# 780-00012-P4_Sch_M2_Focus_Drive.net
KiCad netlist of a schematic drawn in Altium Designer
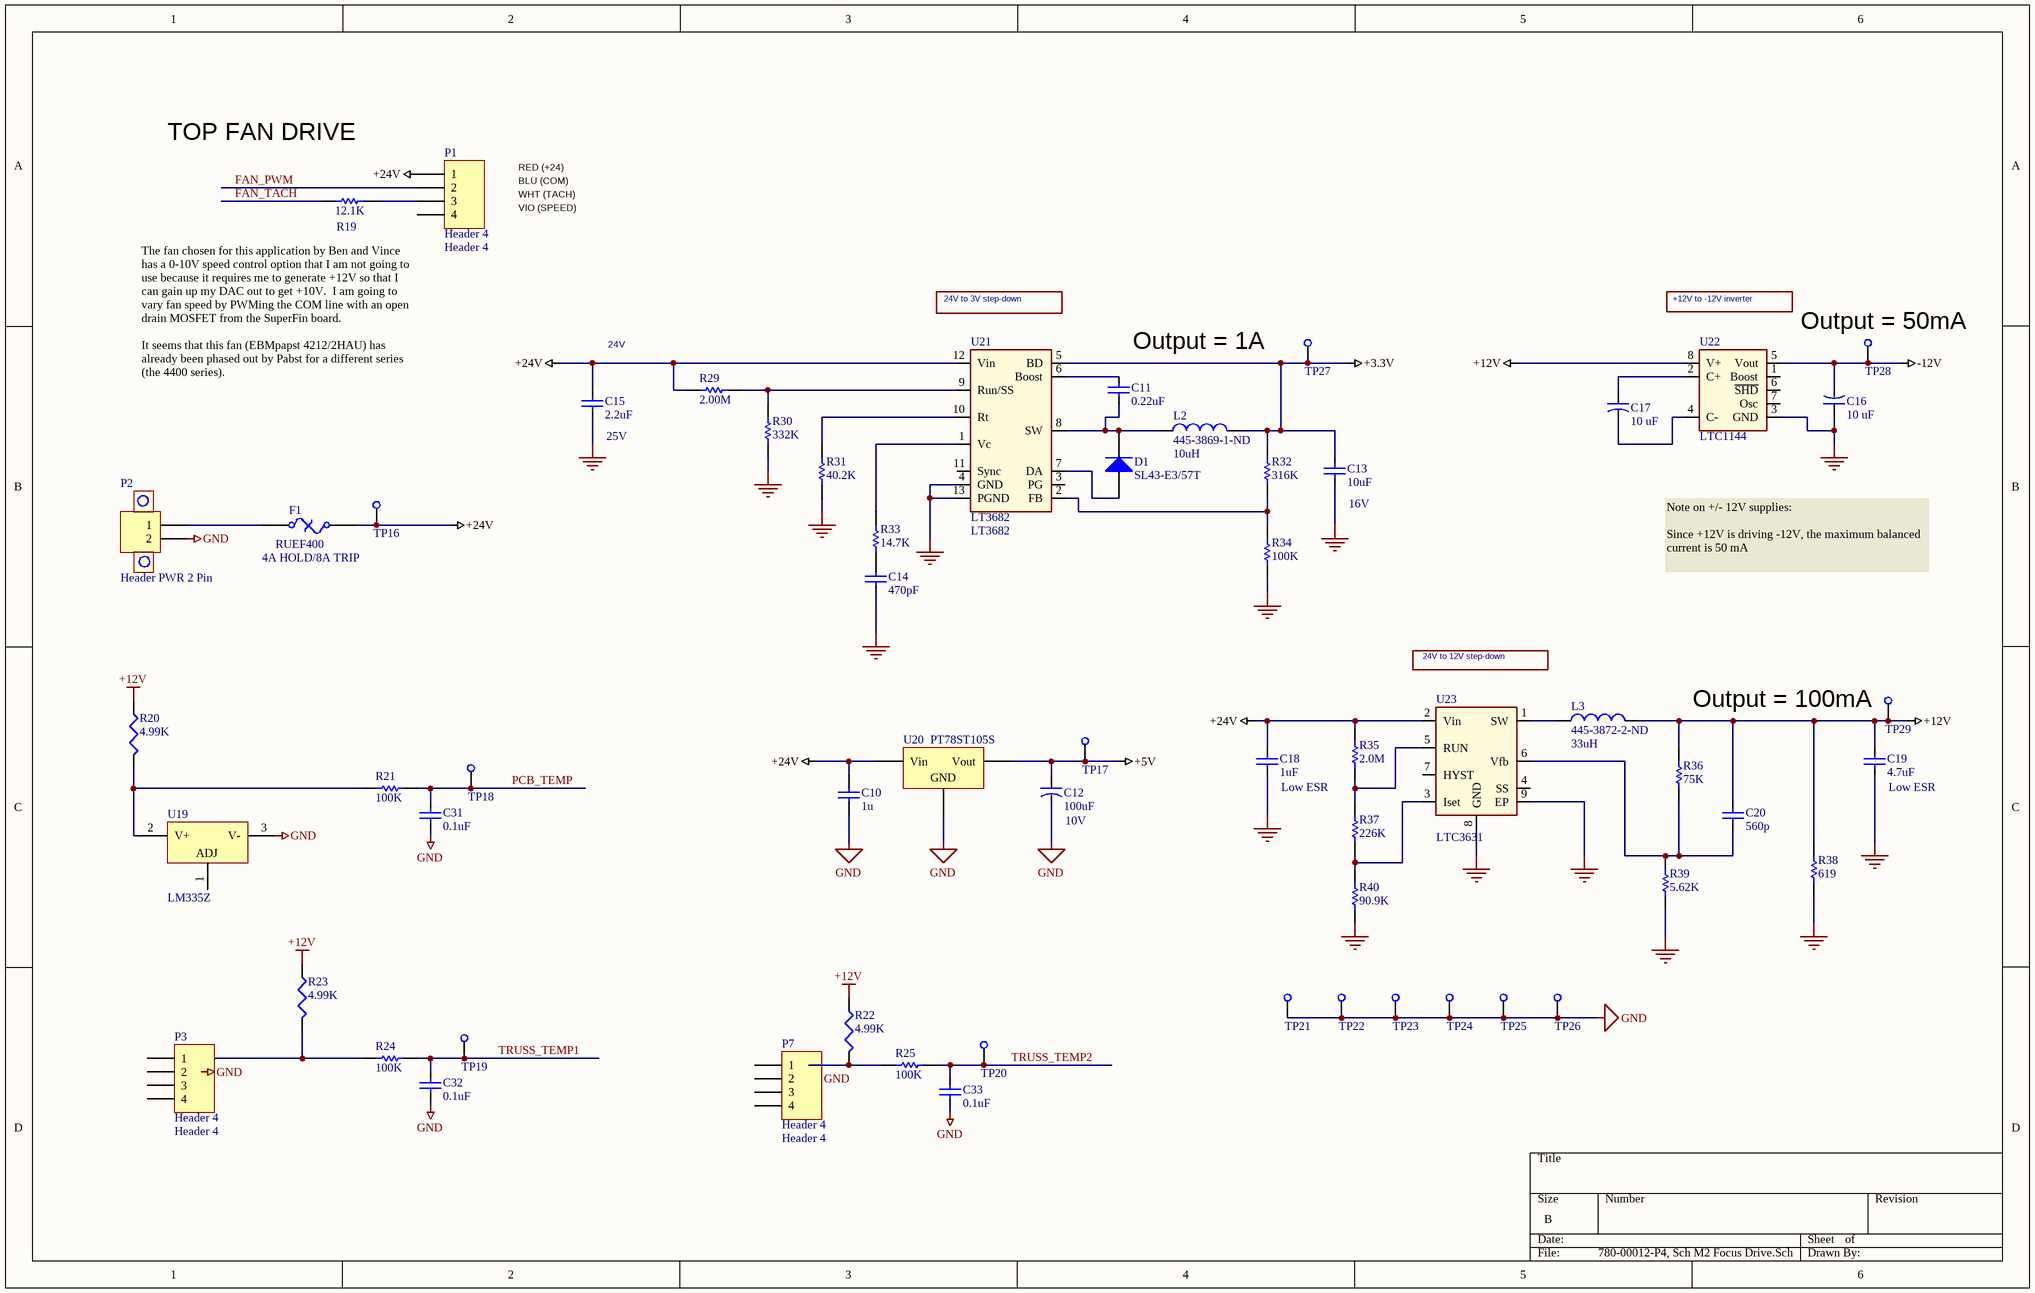
[diagram p0: 780-00012-P4, Sch M2 Focus Drive.SchDoc]

(export (version "E")
  (design (tool "Eeschema 10.0.6"))
  (components
    (comp (ref "C10")
      (value "1u")
      (footprint "2012[0805]")
      (description "Capacitor")
      (fields (field (name "MANUFACTURER") "Taiyo Yuden"))
      (libsource (lib "Miscellaneous Devices") (part "Cap"))
    )
    (comp (ref "C11")
      (value "0.22uF")
      (footprint "SMD_0805")
      (description "Capacitor")
      (fields (field (name "Comment") "Cap SMD"))
      (libsource (lib "Richs Schematic Components") (part "Cap SMD"))
    )
    (comp (ref "C12")
      (value "10V")
      (footprint "SMD_CAP_7343")
      (description "outline 6.0mm x 3.2mm")
      (fields (field (name "MANUFACTURER") "kEMET") (field (name "ALTIUM_VALUE") "100uF"))
      (libsource (lib "Richs Schematic Components") (part "Cap Tant 35V"))
    )
    (comp (ref "C13")
      (value "16V")
      (footprint "SMD_0805")
      (description "Capacitor")
      (fields (field (name "ALTIUM_VALUE") "10uF"))
      (libsource (lib "Richs Schematic Components") (part "Cap SMD"))
    )
    (comp (ref "C14")
      (value "470pF")
      (footprint "SMD_0805")
      (description "Capacitor")
      (fields (field (name "Comment") "Cap SMD"))
      (libsource (lib "Richs Schematic Components") (part "Cap SMD"))
    )
    (comp (ref "C15")
      (value "25V")
      (footprint "SMD_0805")
      (description "Capacitor")
      (fields (field (name "MANUFACTURER") "Taiyo Yuden") (field (name "ALTIUM_VALUE") "2.2uF"))
      (libsource (lib "Richs Schematic Components") (part "Cap SMD"))
    )
    (comp (ref "C16")
      (value "10 uF")
      (footprint "SMD_CAP_3216")
      (description "outline 3.2mm x 1.6mm")
      (fields (field (name "MANUFACTURER") "KEMET") (field (name "Comment") "16V"))
      (libsource (lib "Richs Schematic Components") (part "Cap Tant 16V"))
    )
    (comp (ref "C17")
      (value "10 uF")
      (footprint "SMD_CAP_3216")
      (description "outline 3.2mm x 1.6mm")
      (fields (field (name "MANUFACTURER") "KEMET") (field (name "Comment") "16V"))
      (libsource (lib "Richs Schematic Components") (part "Cap Tant 16V"))
    )
    (comp (ref "C18")
      (value "Low ESR")
      (footprint "SMD_1206")
      (description "Capacitor")
      (fields (field (name "MANUFACTURER") "TDK") (field (name "ALTIUM_VALUE") "1uF"))
      (libsource (lib "Richs Schematic Components") (part "Cap SMD"))
    )
    (comp (ref "C19")
      (value "Low ESR")
      (footprint "SMD_1206")
      (description "Capacitor")
      (fields (field (name "MANUFACTURER") "TDK") (field (name "ALTIUM_VALUE") "4.7uF"))
      (libsource (lib "Richs Schematic Components") (part "Cap SMD"))
    )
    (comp (ref "C20")
      (value "560p")
      (footprint "SMD_0805")
      (description "Capacitor")
      (fields (field (name "Comment") "Cap SMD"))
      (libsource (lib "Richs Schematic Components") (part "Cap SMD"))
    )
    (comp (ref "C31")
      (value "0.1uF")
      (footprint "SMD_0805")
      (description "Capacitor")
      (fields (field (name "MANUFACTURER") "AVX") (field (name "Comment") "Cap SMD"))
      (libsource (lib "Richs Schematic Components") (part "Cap SMD"))
    )
    (comp (ref "C32")
      (value "0.1uF")
      (footprint "SMD_0805")
      (description "Capacitor")
      (fields (field (name "MANUFACTURER") "AVX") (field (name "Comment") "Cap SMD"))
      (libsource (lib "Richs Schematic Components") (part "Cap SMD"))
    )
    (comp (ref "C33")
      (value "0.1uF")
      (footprint "SMD_0805")
      (description "Capacitor")
      (fields (field (name "MANUFACTURER") "AVX") (field (name "Comment") "Cap SMD"))
      (libsource (lib "Richs Schematic Components") (part "Cap SMD"))
    )
    (comp (ref "D1")
      (value "SL43-E3/57T")
      (footprint "SMC")
      (description "Default Diode")
      (fields (field (name "MANUFACTURER") "Vishay/Dale"))
      (libsource (lib "Miscellaneous Devices") (part "Diode"))
    )
    (comp (ref "F1")
      (value "RUEF400")
      (footprint "PolySwitch Radial 0.2")
      (description "PolySwitch RUE Series")
      (fields
        (field (name "MANUFACTURER") "Tyco Electronics")
        (field (name "ALTIUM_VALUE") "4A HOLD/8A TRIP")
      )
      (libsource (lib "Richs Schematic Components") (part "Fuse Thermal"))
    )
    (comp (ref "L2")
      (value "445-3869-1-ND")
      (footprint "Inductor TDC SLF")
      (description "Inductor")
      (fields (field (name "MANUFACTURER") "TDK") (field (name "ALTIUM_VALUE") "10uH"))
      (libsource (lib "Richs Schematic Components") (part "Inductor SMD 10uH 1.8A"))
    )
    (comp (ref "L3")
      (value "445-3872-2-ND")
      (footprint "Inductor TDC SLF")
      (description "Inductor")
      (fields (field (name "MANUFACTURER") "TDK") (field (name "ALTIUM_VALUE") "33uH"))
      (libsource (lib "Richs Schematic Components") (part "Inductor SMD 10uH 1.8A"))
    )
    (comp (ref "P1")
      (value "Header 4")
      (footprint "HDR1X4 for IDC")
      (description "Header, 4-Pin")
      (fields (field (name "ALTIUM_VALUE") "Header 4"))
      (libsource (lib "Richs Schematic Components") (part "Header 4"))
    )
    (comp (ref "P2")
      (value "Header PWR 2 Pin")
      (footprint "HDR-2 pin w/screw")
      (description "Header, 2-Pin")
      (libsource (lib "Richs Schematic Components") (part "Header 2 PWR"))
    )
    (comp (ref "P3")
      (value "Header 4")
      (footprint "HDR1X4 for IDC")
      (description "Header, 4-Pin")
      (fields (field (name "ALTIUM_VALUE") "Header 4"))
      (libsource (lib "Richs Schematic Components") (part "Header 4"))
    )
    (comp (ref "P7")
      (value "Header 4")
      (footprint "HDR1X4 for IDC")
      (description "Header, 4-Pin")
      (fields (field (name "ALTIUM_VALUE") "Header 4"))
      (libsource (lib "Richs Schematic Components") (part "Header 4"))
    )
    (comp (ref "R19")
      (value "12.1K")
      (footprint "SMD_0805")
      (description "Resistor 0805")
      (fields (field (name "MANUFACTURER") "Vishay/Dale") (field (name "Comment") "Res 0805"))
      (libsource (lib "Richs Schematic Components") (part "Res SMD"))
    )
    (comp (ref "R20")
      (value "4.99K")
      (footprint "smd_0805")
      (description "Resistor")
      (fields (field (name "MANUFACTURER") "DALE") (field (name "Comment") "Res3"))
      (libsource (lib "Miscellaneous Devices") (part "Res3"))
    )
    (comp (ref "R21")
      (value "100K")
      (footprint "SMD_0805")
      (description "Resistor")
      (fields (field (name "MANUFACTURER") "Vishay/Dale") (field (name "Comment") "Res SMD"))
      (libsource (lib "Richs Schematic Components") (part "Res SMD"))
    )
    (comp (ref "R22")
      (value "4.99K")
      (footprint "smd_0805")
      (description "Resistor")
      (fields (field (name "MANUFACTURER") "DALE") (field (name "Comment") "Res3"))
      (libsource (lib "Miscellaneous Devices") (part "Res3"))
    )
    (comp (ref "R23")
      (value "4.99K")
      (footprint "smd_0805")
      (description "Resistor")
      (fields (field (name "MANUFACTURER") "DALE") (field (name "Comment") "Res3"))
      (libsource (lib "Miscellaneous Devices") (part "Res3"))
    )
    (comp (ref "R24")
      (value "100K")
      (footprint "SMD_0805")
      (description "Resistor")
      (fields (field (name "MANUFACTURER") "Vishay/Dale") (field (name "Comment") "Res SMD"))
      (libsource (lib "Richs Schematic Components") (part "Res SMD"))
    )
    (comp (ref "R25")
      (value "100K")
      (footprint "SMD_0805")
      (description "Resistor")
      (fields (field (name "MANUFACTURER") "Vishay/Dale") (field (name "Comment") "Res SMD"))
      (libsource (lib "Richs Schematic Components") (part "Res SMD"))
    )
    (comp (ref "R29")
      (value "2.00M")
      (footprint "SMD_0805")
      (description "Resistor 0805")
      (fields (field (name "MANUFACTURER") "Vishay/Dale") (field (name "Comment") "Res 0805"))
      (libsource (lib "Richs Schematic Components") (part "Res SMD"))
    )
    (comp (ref "R30")
      (value "332K")
      (footprint "SMD_0805")
      (description "Resistor 0805")
      (fields (field (name "MANUFACTURER") "Vishay/Dale") (field (name "Comment") "Res 0805"))
      (libsource (lib "Richs Schematic Components") (part "Res SMD"))
    )
    (comp (ref "R31")
      (value "40.2K")
      (footprint "SMD_0805")
      (description "Resistor 0805")
      (fields (field (name "MANUFACTURER") "Vishay/Dale") (field (name "Comment") "Res 0805"))
      (libsource (lib "Richs Schematic Components") (part "Res SMD"))
    )
    (comp (ref "R32")
      (value "316K")
      (footprint "SMD_0805")
      (description "Resistor 0805")
      (fields (field (name "MANUFACTURER") "Vishay/Dale") (field (name "Comment") "Res 0805"))
      (libsource (lib "Richs Schematic Components") (part "Res SMD"))
    )
    (comp (ref "R33")
      (value "14.7K")
      (footprint "SMD_0805")
      (description "Resistor 0805")
      (fields (field (name "MANUFACTURER") "Vishay/Dale") (field (name "Comment") "Res 0805"))
      (libsource (lib "Richs Schematic Components") (part "Res SMD"))
    )
    (comp (ref "R34")
      (value "100K")
      (footprint "SMD_0805")
      (description "Resistor 0805")
      (fields (field (name "MANUFACTURER") "Vishay/Dale") (field (name "Comment") "Res 0805"))
      (libsource (lib "Richs Schematic Components") (part "Res SMD"))
    )
    (comp (ref "R35")
      (value "2.0M")
      (footprint "SMD_0805")
      (description "Resistor 0805")
      (fields (field (name "MANUFACTURER") "Vishay/Dale") (field (name "Comment") "Res 0805"))
      (libsource (lib "Richs Schematic Components") (part "Res SMD"))
    )
    (comp (ref "R36")
      (value "75K")
      (footprint "SMD_0805")
      (description "Resistor 0805")
      (fields (field (name "MANUFACTURER") "Vishay/Dale") (field (name "Comment") "Res 0805"))
      (libsource (lib "Richs Schematic Components") (part "Res SMD"))
    )
    (comp (ref "R37")
      (value "226K")
      (footprint "SMD_0805")
      (description "Resistor 0805")
      (fields (field (name "MANUFACTURER") "Vishay/Dale") (field (name "Comment") "Res 0805"))
      (libsource (lib "Richs Schematic Components") (part "Res SMD"))
    )
    (comp (ref "R38")
      (value "619")
      (footprint "SMD_0805")
      (description "Resistor 0805")
      (fields (field (name "MANUFACTURER") "Vishay/Dale") (field (name "Comment") "Res 0805"))
      (libsource (lib "Richs Schematic Components") (part "Res SMD"))
    )
    (comp (ref "R39")
      (value "5.62K")
      (footprint "SMD_0805")
      (description "Resistor 0805")
      (fields (field (name "MANUFACTURER") "Vishay/Dale") (field (name "Comment") "Res 0805"))
      (libsource (lib "Richs Schematic Components") (part "Res SMD"))
    )
    (comp (ref "R40")
      (value "90.9K")
      (footprint "SMD_0805")
      (description "Resistor 0805")
      (fields (field (name "MANUFACTURER") "Vishay/Dale") (field (name "Comment") "Res 0805"))
      (libsource (lib "Richs Schematic Components") (part "Res SMD"))
    )
    (comp (ref "TP16")
      (value "Test Point SMD")
      (footprint "SMD_TEST POINT")
      (description "SMD loop test point")
      (libsource (lib "Richs Schematic Components") (part "Test Point SMD"))
    )
    (comp (ref "TP17")
      (value "Test Point SMD")
      (footprint "SMD_TEST POINT")
      (description "SMD loop test point")
      (libsource (lib "Richs Schematic Components") (part "Test Point SMD"))
    )
    (comp (ref "TP18")
      (value "Test Point SMD")
      (footprint "SMD_TEST POINT")
      (description "SMD loop test point")
      (libsource (lib "Richs Schematic Components") (part "Test Point SMD"))
    )
    (comp (ref "TP19")
      (value "Test Point SMD")
      (footprint "SMD_TEST POINT")
      (description "SMD loop test point")
      (libsource (lib "Richs Schematic Components") (part "Test Point SMD"))
    )
    (comp (ref "TP20")
      (value "Test Point SMD")
      (footprint "SMD_TEST POINT")
      (description "SMD loop test point")
      (libsource (lib "Richs Schematic Components") (part "Test Point SMD"))
    )
    (comp (ref "TP21")
      (value "Test Point SMD")
      (footprint "SMD_TEST POINT")
      (description "SMD loop test point")
      (libsource (lib "Richs Schematic Components") (part "Test Point SMD"))
    )
    (comp (ref "TP22")
      (value "Test Point SMD")
      (footprint "SMD_TEST POINT")
      (description "SMD loop test point")
      (libsource (lib "Richs Schematic Components") (part "Test Point SMD"))
    )
    (comp (ref "TP23")
      (value "Test Point SMD")
      (footprint "SMD_TEST POINT")
      (description "SMD loop test point")
      (libsource (lib "Richs Schematic Components") (part "Test Point SMD"))
    )
    (comp (ref "TP24")
      (value "Test Point SMD")
      (footprint "SMD_TEST POINT")
      (description "SMD loop test point")
      (libsource (lib "Richs Schematic Components") (part "Test Point SMD"))
    )
    (comp (ref "TP25")
      (value "Test Point SMD")
      (footprint "SMD_TEST POINT")
      (description "SMD loop test point")
      (libsource (lib "Richs Schematic Components") (part "Test Point SMD"))
    )
    (comp (ref "TP26")
      (value "Test Point SMD")
      (footprint "SMD_TEST POINT")
      (description "SMD loop test point")
      (libsource (lib "Richs Schematic Components") (part "Test Point SMD"))
    )
    (comp (ref "TP27")
      (value "Test Point SMD")
      (footprint "SMD_TEST POINT")
      (description "SMD loop test point")
      (libsource (lib "Richs Schematic Components") (part "Test Point SMD"))
    )
    (comp (ref "TP28")
      (value "Test Point SMD")
      (footprint "SMD_TEST POINT")
      (description "SMD loop test point")
      (libsource (lib "Richs Schematic Components") (part "Test Point SMD"))
    )
    (comp (ref "TP29")
      (value "Test Point SMD")
      (footprint "SMD_TEST POINT")
      (description "SMD loop test point")
      (libsource (lib "Richs Schematic Components") (part "Test Point SMD"))
    )
    (comp (ref "U19")
      (value "LM335Z")
      (footprint "Z03A")
      (description "Precision Temperature Sensor")
      (fields (field (name "MANUFACTURER") "National Semiconductor"))
      (libsource (lib "NSC Temperature Sensor") (part "LM335Z"))
    )
    (comp (ref "U20")
      (value "PT78ST105S")
      (footprint "PSIP_3_SMD")
      (description "Voltage Regulator")
      (fields (field (name "MANUFACTURER") "Texas Instruments"))
      (libsource (lib "Miscellaneous Devices") (part "Volt Reg"))
    )
    (comp (ref "U21")
      (value "LT3682")
      (footprint "DD12/DFN12")
      (description "1A uPwr Step-Down switching regulator")
      (fields (field (name "MANUFACTURER") "Linear") (field (name "ALTIUM_VALUE") "LT3682"))
      (libsource (lib "Richs Schematic Components") (part "LT3682"))
    )
    (comp (ref "U22")
      (value "LTC1144")
      (footprint "S8_M")
      (description "IC VOLT CONV SW-CAP W/SHTDN8SOIC")
      (fields (field (name "MANUFACTURER") "Linear"))
      (libsource (lib "Richs Schematic Components") (part "LTC1144"))
    )
    (comp (ref "U23")
      (value "LTC3631")
      (footprint "DD8/DFN8")
      (description "IC CONV STP-DWN ADJ 8-DFN")
      (fields (field (name "MANUFACTURER") "Linear"))
      (libsource (lib "Richs Schematic Components") (part "LTC3631"))
    )
  )
  (nets
    (net (code "1") (name "+3.3V") (class "Default")
      (node (ref "C13") (pin "2") (pinfunction "2_2") (pintype "passive"))
      (node (ref "L2") (pin "2") (pinfunction "2_2") (pintype "passive"))
      (node (ref "R32") (pin "2") (pinfunction "2_2") (pintype "passive"))
      (node (ref "TP27") (pin "1") (pinfunction "TP_1") (pintype "passive"))
      (node (ref "U21") (pin "5") (pinfunction "BD_5") (pintype "passive"))
    )
    (net (code "2") (name "+5V") (class "Default")
      (node (ref "C12") (pin "pos") (pinfunction "1_pos") (pintype "passive"))
      (node (ref "TP17") (pin "1") (pinfunction "TP_1") (pintype "passive"))
      (node (ref "U20") (pin "3") (pinfunction "Vout_3") (pintype "passive"))
    )
    (net (code "3") (name "+12V") (class "Default")
      (node (ref "C19") (pin "2") (pinfunction "2_2") (pintype "passive"))
      (node (ref "C20") (pin "2") (pinfunction "2_2") (pintype "passive"))
      (node (ref "L3") (pin "2") (pinfunction "2_2") (pintype "passive"))
      (node (ref "R20") (pin "1") (pinfunction "1_1") (pintype "passive"))
      (node (ref "R22") (pin "1") (pinfunction "1_1") (pintype "passive"))
      (node (ref "R23") (pin "1") (pinfunction "1_1") (pintype "passive"))
      (node (ref "R36") (pin "2") (pinfunction "2_2") (pintype "passive"))
      (node (ref "R38") (pin "2") (pinfunction "2_2") (pintype "passive"))
      (node (ref "TP29") (pin "1") (pinfunction "TP_1") (pintype "passive"))
      (node (ref "U22") (pin "8") (pinfunction "V+_8") (pintype "power_in"))
    )
    (net (code "4") (name "+24V") (class "Default")
      (node (ref "C10") (pin "1") (pinfunction "1_1") (pintype "passive"))
      (node (ref "C15") (pin "2") (pinfunction "2_2") (pintype "passive"))
      (node (ref "C18") (pin "2") (pinfunction "2_2") (pintype "passive"))
      (node (ref "F1") (pin "2") (pinfunction "2_2") (pintype "passive"))
      (node (ref "P1") (pin "1") (pinfunction "1_1") (pintype "passive"))
      (node (ref "R29") (pin "1") (pinfunction "1_1") (pintype "passive"))
      (node (ref "R35") (pin "2") (pinfunction "2_2") (pintype "passive"))
      (node (ref "TP16") (pin "1") (pinfunction "TP_1") (pintype "passive"))
      (node (ref "U20") (pin "1") (pinfunction "Vin_1") (pintype "passive"))
      (node (ref "U21") (pin "12") (pinfunction "Vin_12") (pintype "passive"))
      (node (ref "U23") (pin "2") (pinfunction "Vin_2") (pintype "passive"))
    )
    (net (code "5") (name "-12V") (class "Default")
      (node (ref "C16") (pin "2") (pinfunction "2_2") (pintype "passive"))
      (node (ref "TP28") (pin "1") (pinfunction "TP_1") (pintype "passive"))
      (node (ref "U22") (pin "5") (pinfunction "Vout_5") (pintype "passive"))
    )
    (net (code "6") (name "/FAN_PWM") (class "Default")
      (node (ref "P1") (pin "2") (pinfunction "2_2") (pintype "passive"))
    )
    (net (code "7") (name "/FAN_TACH") (class "Default")
      (node (ref "R19") (pin "1") (pinfunction "1_1") (pintype "passive"))
    )
    (net (code "8") (name "/PCB_TEMP") (class "Default")
      (node (ref "C31") (pin "2") (pinfunction "2_2") (pintype "passive"))
      (node (ref "R21") (pin "1") (pinfunction "1_1") (pintype "passive"))
      (node (ref "TP18") (pin "1") (pinfunction "TP_1") (pintype "passive"))
    )
    (net (code "9") (name "/TRUSS_TEMP1") (class "Default")
      (node (ref "C32") (pin "2") (pinfunction "2_2") (pintype "passive"))
      (node (ref "R24") (pin "1") (pinfunction "1_1") (pintype "passive"))
      (node (ref "TP19") (pin "1") (pinfunction "TP_1") (pintype "passive"))
    )
    (net (code "10") (name "/TRUSS_TEMP2") (class "Default")
      (node (ref "C33") (pin "2") (pinfunction "2_2") (pintype "passive"))
      (node (ref "R25") (pin "1") (pinfunction "1_1") (pintype "passive"))
      (node (ref "TP20") (pin "1") (pinfunction "TP_1") (pintype "passive"))
    )
    (net (code "11") (name "GND") (class "Default")
      (node (ref "C10") (pin "2") (pinfunction "2_2") (pintype "passive"))
      (node (ref "C12") (pin "neg") (pinfunction "2_neg") (pintype "passive"))
      (node (ref "C13") (pin "1") (pinfunction "1_1") (pintype "passive"))
      (node (ref "C14") (pin "1") (pinfunction "1_1") (pintype "passive"))
      (node (ref "C15") (pin "1") (pinfunction "1_1") (pintype "passive"))
      (node (ref "C16") (pin "1") (pinfunction "1_1") (pintype "passive"))
      (node (ref "C18") (pin "1") (pinfunction "1_1") (pintype "passive"))
      (node (ref "C19") (pin "1") (pinfunction "1_1") (pintype "passive"))
      (node (ref "C31") (pin "1") (pinfunction "1_1") (pintype "passive"))
      (node (ref "C32") (pin "1") (pinfunction "1_1") (pintype "passive"))
      (node (ref "C33") (pin "1") (pinfunction "1_1") (pintype "passive"))
      (node (ref "P2") (pin "2") (pinfunction "2_2") (pintype "passive"))
      (node (ref "R30") (pin "1") (pinfunction "1_1") (pintype "passive"))
      (node (ref "R31") (pin "1") (pinfunction "1_1") (pintype "passive"))
      (node (ref "R34") (pin "1") (pinfunction "1_1") (pintype "passive"))
      (node (ref "R38") (pin "1") (pinfunction "1_1") (pintype "passive"))
      (node (ref "R39") (pin "1") (pinfunction "1_1") (pintype "passive"))
      (node (ref "R40") (pin "1") (pinfunction "1_1") (pintype "passive"))
      (node (ref "TP21") (pin "1") (pinfunction "TP_1") (pintype "passive"))
      (node (ref "TP22") (pin "1") (pinfunction "TP_1") (pintype "passive"))
      (node (ref "TP23") (pin "1") (pinfunction "TP_1") (pintype "passive"))
      (node (ref "TP24") (pin "1") (pinfunction "TP_1") (pintype "passive"))
      (node (ref "TP25") (pin "1") (pinfunction "TP_1") (pintype "passive"))
      (node (ref "TP26") (pin "1") (pinfunction "TP_1") (pintype "passive"))
      (node (ref "U19") (pin "3") (pinfunction "V-_3") (pintype "passive"))
      (node (ref "U20") (pin "2") (pinfunction "GND_2") (pintype "passive"))
      (node (ref "U21") (pin "13") (pinfunction "PGND_13") (pintype "passive"))
      (node (ref "U21") (pin "4") (pinfunction "GND_4") (pintype "power_in"))
      (node (ref "U22") (pin "3") (pinfunction "GND_3") (pintype "passive"))
      (node (ref "U23") (pin "8") (pinfunction "GND_8") (pintype "passive"))
      (node (ref "U23") (pin "9") (pinfunction "EP_9") (pintype "passive"))
    )
    (net (code "12") (name "Net-(C14-Pad2)") (class "Default")
      (node (ref "C14") (pin "2") (pinfunction "2_2") (pintype "passive"))
      (node (ref "R33") (pin "1") (pinfunction "1_1") (pintype "passive"))
    )
    (net (code "13") (name "Net-(D1-A)") (class "Default")
      (node (ref "D1") (pin "1") (pinfunction "A_1") (pintype "passive"))
      (node (ref "U21") (pin "7") (pinfunction "DA_7") (pintype "passive"))
    )
    (net (code "14") (name "Net-(D1-K)") (class "Default")
      (node (ref "C11") (pin "1") (pinfunction "1_1") (pintype "passive"))
      (node (ref "D1") (pin "2") (pinfunction "K_2") (pintype "passive"))
      (node (ref "L2") (pin "1") (pinfunction "1_1") (pintype "passive"))
      (node (ref "U21") (pin "8") (pinfunction "SW_8") (pintype "passive"))
    )
    (net (code "15") (name "Net-(F1-Pad1)") (class "Default")
      (node (ref "F1") (pin "1") (pinfunction "1_1") (pintype "passive"))
      (node (ref "P2") (pin "1") (pinfunction "1_1") (pintype "passive"))
    )
    (net (code "16") (name "Net-(P1-Pad3)") (class "Default")
      (node (ref "P1") (pin "3") (pinfunction "3_3") (pintype "passive"))
      (node (ref "R19") (pin "2") (pinfunction "2_2") (pintype "passive"))
    )
    (net (code "17") (name "Net-(R22-Pad2)") (class "Default")
      (node (ref "R22") (pin "2") (pinfunction "2_2") (pintype "passive"))
      (node (ref "R25") (pin "2") (pinfunction "2_2") (pintype "passive"))
    )
    (net (code "18") (name "Net-(R23-Pad2)") (class "Default")
      (node (ref "R23") (pin "2") (pinfunction "2_2") (pintype "passive"))
      (node (ref "R24") (pin "2") (pinfunction "2_2") (pintype "passive"))
    )
    (net (code "19") (name "Net-(U19-V+)") (class "Default")
      (node (ref "R20") (pin "2") (pinfunction "2_2") (pintype "passive"))
      (node (ref "R21") (pin "2") (pinfunction "2_2") (pintype "passive"))
      (node (ref "U19") (pin "2") (pinfunction "V+_2") (pintype "passive"))
    )
    (net (code "20") (name "Net-(U21-Boost)") (class "Default")
      (node (ref "C11") (pin "2") (pinfunction "2_2") (pintype "passive"))
      (node (ref "U21") (pin "6") (pinfunction "Boost_6") (pintype "passive"))
    )
    (net (code "21") (name "Net-(U21-FB)") (class "Default")
      (node (ref "R32") (pin "1") (pinfunction "1_1") (pintype "passive"))
      (node (ref "R34") (pin "2") (pinfunction "2_2") (pintype "passive"))
      (node (ref "U21") (pin "2") (pinfunction "FB_2") (pintype "passive"))
    )
    (net (code "22") (name "Net-(U21-Rt)") (class "Default")
      (node (ref "R31") (pin "2") (pinfunction "2_2") (pintype "passive"))
      (node (ref "U21") (pin "10") (pinfunction "Rt_10") (pintype "passive"))
    )
    (net (code "23") (name "Net-(U21-Run{slash}SS)") (class "Default")
      (node (ref "R29") (pin "2") (pinfunction "2_2") (pintype "passive"))
      (node (ref "R30") (pin "2") (pinfunction "2_2") (pintype "passive"))
      (node (ref "U21") (pin "9") (pinfunction "Run/SS_9") (pintype "passive"))
    )
    (net (code "24") (name "Net-(U21-Vc)") (class "Default")
      (node (ref "R33") (pin "2") (pinfunction "2_2") (pintype "passive"))
      (node (ref "U21") (pin "1") (pinfunction "Vc_1") (pintype "passive"))
    )
    (net (code "25") (name "Net-(U22-C+)") (class "Default")
      (node (ref "C17") (pin "1") (pinfunction "1_1") (pintype "passive"))
      (node (ref "U22") (pin "2") (pinfunction "C+_2") (pintype "passive"))
    )
    (net (code "26") (name "Net-(U22-C-)") (class "Default")
      (node (ref "C17") (pin "2") (pinfunction "2_2") (pintype "passive"))
      (node (ref "U22") (pin "4") (pinfunction "C-_4") (pintype "passive"))
    )
    (net (code "27") (name "Net-(U23-Iset)") (class "Default")
      (node (ref "R37") (pin "1") (pinfunction "1_1") (pintype "passive"))
      (node (ref "R40") (pin "2") (pinfunction "2_2") (pintype "passive"))
      (node (ref "U23") (pin "3") (pinfunction "Iset_3") (pintype "passive"))
    )
    (net (code "28") (name "Net-(U23-RUN)") (class "Default")
      (node (ref "R35") (pin "1") (pinfunction "1_1") (pintype "passive"))
      (node (ref "R37") (pin "2") (pinfunction "2_2") (pintype "passive"))
      (node (ref "U23") (pin "5") (pinfunction "RUN_5") (pintype "passive"))
    )
    (net (code "29") (name "Net-(U23-SW)") (class "Default")
      (node (ref "L3") (pin "1") (pinfunction "1_1") (pintype "passive"))
      (node (ref "U23") (pin "1") (pinfunction "SW_1") (pintype "passive"))
    )
    (net (code "30") (name "Net-(U23-Vfb)") (class "Default")
      (node (ref "C20") (pin "1") (pinfunction "1_1") (pintype "passive"))
      (node (ref "R36") (pin "1") (pinfunction "1_1") (pintype "passive"))
      (node (ref "R39") (pin "2") (pinfunction "2_2") (pintype "passive"))
      (node (ref "U23") (pin "6") (pinfunction "Vfb_6") (pintype "passive"))
    )
    (net (code "31") (name "SUPPORT") (class "Default")
      (node (ref "U20") (pin "0") (pinfunction "SUPPORT_0") (pintype "passive"))
    )
    (net (code "32") (name "unconnected-(P1-Pad4)") (class "Default")
      (node (ref "P1") (pin "4") (pinfunction "4_4") (pintype "passive"))
    )
    (net (code "33") (name "unconnected-(P3-Pad1)") (class "Default")
      (node (ref "P3") (pin "1") (pinfunction "1_1") (pintype "passive"))
    )
    (net (code "34") (name "unconnected-(P3-Pad2)") (class "Default")
      (node (ref "P3") (pin "2") (pinfunction "2_2") (pintype "passive"))
    )
    (net (code "35") (name "unconnected-(P3-Pad3)") (class "Default")
      (node (ref "P3") (pin "3") (pinfunction "3_3") (pintype "passive"))
    )
    (net (code "36") (name "unconnected-(P3-Pad4)") (class "Default")
      (node (ref "P3") (pin "4") (pinfunction "4_4") (pintype "passive"))
    )
    (net (code "37") (name "unconnected-(P7-Pad1)") (class "Default")
      (node (ref "P7") (pin "1") (pinfunction "1_1") (pintype "passive"))
    )
    (net (code "38") (name "unconnected-(P7-Pad2)") (class "Default")
      (node (ref "P7") (pin "2") (pinfunction "2_2") (pintype "passive"))
    )
    (net (code "39") (name "unconnected-(P7-Pad3)") (class "Default")
      (node (ref "P7") (pin "3") (pinfunction "3_3") (pintype "passive"))
    )
    (net (code "40") (name "unconnected-(P7-Pad4)") (class "Default")
      (node (ref "P7") (pin "4") (pinfunction "4_4") (pintype "passive"))
    )
    (net (code "41") (name "unconnected-(U19-ADJ-Pad1)") (class "Default")
      (node (ref "U19") (pin "1") (pinfunction "ADJ_1") (pintype "passive"))
    )
    (net (code "42") (name "unconnected-(U21-PG-Pad3)") (class "Default")
      (node (ref "U21") (pin "3") (pinfunction "PG_3") (pintype "passive"))
    )
    (net (code "43") (name "unconnected-(U21-Sync-Pad11)") (class "Default")
      (node (ref "U21") (pin "11") (pinfunction "Sync_11") (pintype "passive"))
    )
    (net (code "44") (name "unconnected-(U22-Boost-Pad1)") (class "Default")
      (node (ref "U22") (pin "1") (pinfunction "Boost_1") (pintype "passive"))
    )
    (net (code "45") (name "unconnected-(U22-Osc-Pad7)") (class "Default")
      (node (ref "U22") (pin "7") (pinfunction "Osc_7") (pintype "passive"))
    )
    (net (code "46") (name "unconnected-(U22-~{SHD}-Pad6)") (class "Default")
      (node (ref "U22") (pin "6") (pinfunction "~{SHD}_6") (pintype "passive"))
    )
    (net (code "47") (name "unconnected-(U23-HYST-Pad7)") (class "Default")
      (node (ref "U23") (pin "7") (pinfunction "HYST_7") (pintype "passive"))
    )
    (net (code "48") (name "unconnected-(U23-SS-Pad4)") (class "Default")
      (node (ref "U23") (pin "4") (pinfunction "SS_4") (pintype "passive"))
    )
  )
)
